# STM32Fx.net
KiCad netlist of a schematic drawn in Altium Designer
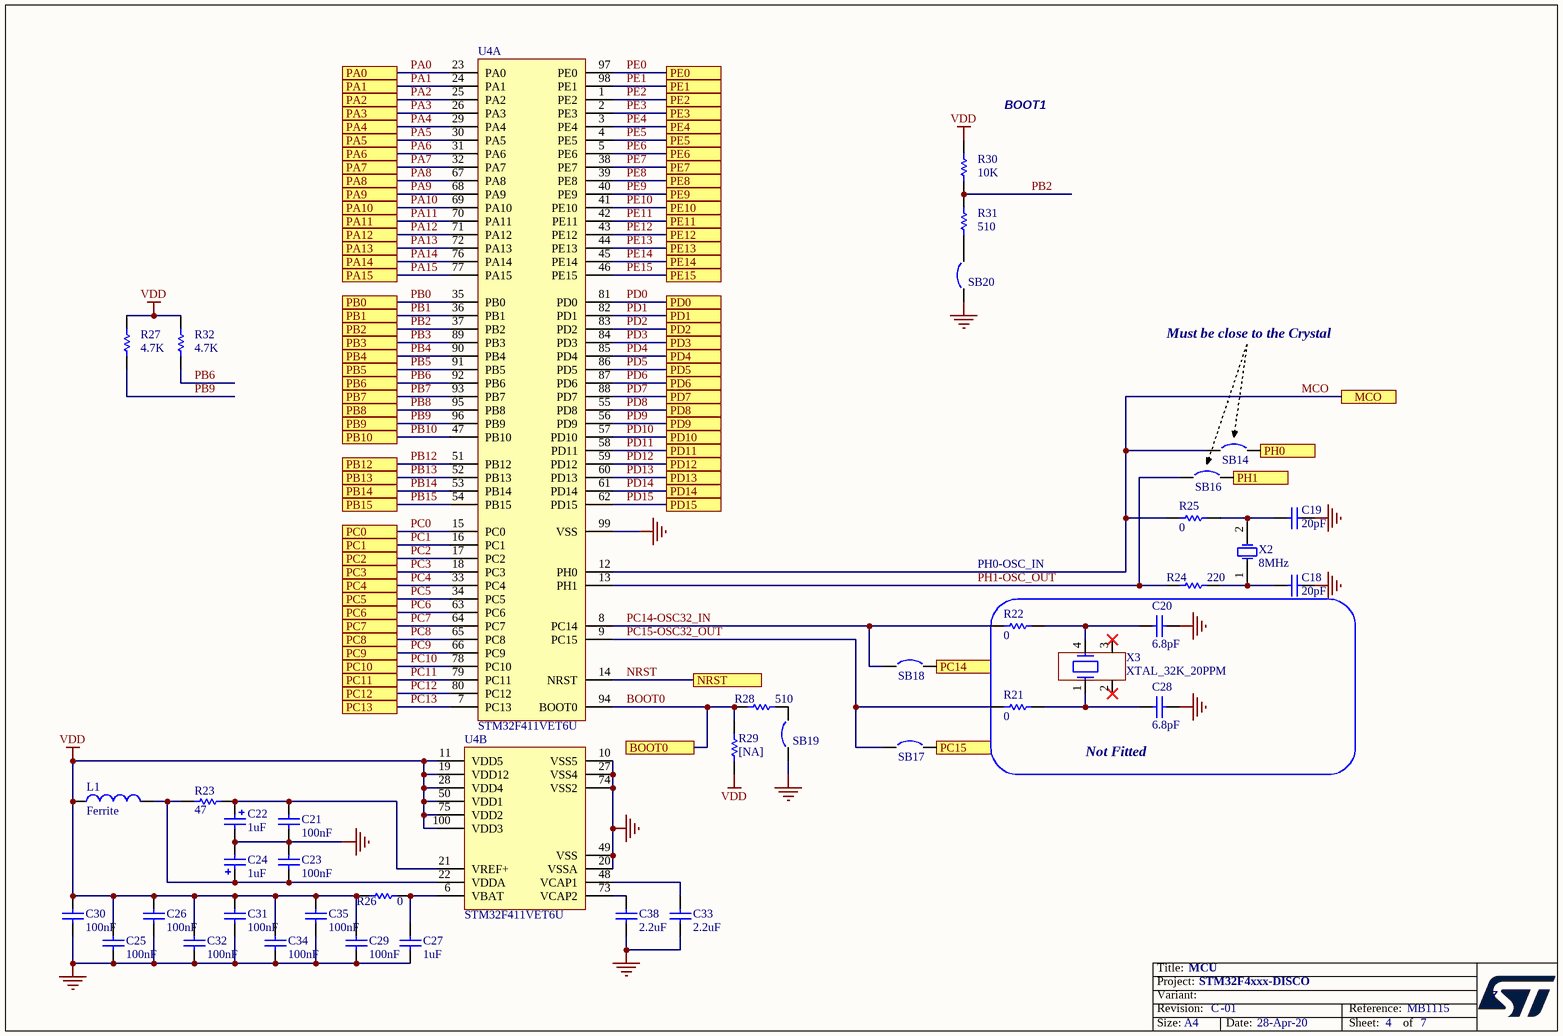
[diagram p0: STM32Fx.SchDoc]

(export (version "E")
  (design (tool "Eeschema 10.0.6"))
  (components
    (comp (ref "C18")
      (value "20pF")
      (footprint "0402C (Primary)")
      (description "Capacitor,20pF,50V,NPO,5%,0402,YAGEO")
      (libsource (lib "MCD_TOOLS") (part "Cap_20pF_NPO_5%_0402"))
    )
    (comp (ref "C19")
      (value "20pF")
      (footprint "0402C (Primary)")
      (description "Capacitor,20pF,50V,NPO,5%,0402,YAGEO")
      (libsource (lib "MCD_TOOLS") (part "Cap_20pF_NPO_5%_0402"))
    )
    (comp (ref "C20")
      (value "6.8pF")
      (footprint "0402C (Primary)")
      (description "Capacitor,6.8pF,50V,NPO,4%,0402,AVX")
      (libsource (lib "MCD_TOOLS") (part "Cap_6.8pF_NPO_4%_0402"))
    )
    (comp (ref "C21")
      (value "100nF")
      (footprint "0402C (Primary)")
      (description "Capacitor,100nF,16V,X7R,10%,0402,YAGEO")
      (libsource (lib "MCD_TOOLS") (part "Cap_100nF_X7R_10%_0402"))
    )
    (comp (ref "C22")
      (value "1uF")
      (footprint "TAN-A (Primary)")
      (description "Polarized Capacitor,1uF,16V,10%,typeA,AVX")
      (libsource (lib "MCD_TOOLS") (part "Cap_1uF_POL_10%_TANA"))
    )
    (comp (ref "C23")
      (value "100nF")
      (footprint "0402C (Primary)")
      (description "Capacitor,100nF,16V,X7R,10%,0402,YAGEO")
      (libsource (lib "MCD_TOOLS") (part "Cap_100nF_X7R_10%_0402"))
    )
    (comp (ref "C24")
      (value "1uF")
      (footprint "TAN-A (Primary)")
      (description "Polarized Capacitor,1uF,16V,10%,typeA,AVX")
      (libsource (lib "MCD_TOOLS") (part "Cap_1uF_POL_10%_TANA"))
    )
    (comp (ref "C25")
      (value "100nF")
      (footprint "0402C (Primary)")
      (description "Capacitor,100nF,16V,X7R,10%,0402,YAGEO")
      (libsource (lib "MCD_TOOLS") (part "Cap_100nF_X7R_10%_0402"))
    )
    (comp (ref "C26")
      (value "100nF")
      (footprint "0402C (Primary)")
      (description "Capacitor,100nF,16V,X7R,10%,0402,YAGEO")
      (libsource (lib "MCD_TOOLS") (part "Cap_100nF_X7R_10%_0402"))
    )
    (comp (ref "C27")
      (value "1uF")
      (footprint "0603C (Primary)")
      (description "Capacitor,1uF,16V,X5R,10%,0603,YAGEO")
      (libsource (lib "MCD_TOOLS") (part "Cap_1uF_X5R_10%_0603"))
    )
    (comp (ref "C28")
      (value "6.8pF")
      (footprint "0402C (Primary)")
      (description "Capacitor,6.8pF,50V,NPO,4%,0402,AVX")
      (libsource (lib "MCD_TOOLS") (part "Cap_6.8pF_NPO_4%_0402"))
    )
    (comp (ref "C29")
      (value "100nF")
      (footprint "0402C (Primary)")
      (description "Capacitor,100nF,16V,X7R,10%,0402,YAGEO")
      (libsource (lib "MCD_TOOLS") (part "Cap_100nF_X7R_10%_0402"))
    )
    (comp (ref "C30")
      (value "100nF")
      (footprint "0402C (Primary)")
      (description "Capacitor,100nF,16V,X7R,10%,0402,YAGEO")
      (libsource (lib "MCD_TOOLS") (part "Cap_100nF_X7R_10%_0402"))
    )
    (comp (ref "C31")
      (value "100nF")
      (footprint "0402C (Primary)")
      (description "Capacitor,100nF,16V,X7R,10%,0402,YAGEO")
      (libsource (lib "MCD_TOOLS") (part "Cap_100nF_X7R_10%_0402"))
    )
    (comp (ref "C32")
      (value "100nF")
      (footprint "0402C (Primary)")
      (description "Capacitor,100nF,16V,X7R,10%,0402,YAGEO")
      (libsource (lib "MCD_TOOLS") (part "Cap_100nF_X7R_10%_0402"))
    )
    (comp (ref "C33")
      (value "2.2uF")
      (footprint "TAN-A (Primary)")
      (description "Capacitor,2.2uF,16V, X7R,10%,0805,YAGEO")
      (libsource (lib "MCD_TOOLS") (part "Cap_2.2uF_X7R_10%_0805"))
    )
    (comp (ref "C34")
      (value "100nF")
      (footprint "0402C (Primary)")
      (description "Capacitor,100nF,16V,X7R,10%,0402,YAGEO")
      (libsource (lib "MCD_TOOLS") (part "Cap_100nF_X7R_10%_0402"))
    )
    (comp (ref "C35")
      (value "100nF")
      (footprint "0402C (Primary)")
      (description "Capacitor,100nF,16V,X7R,10%,0402,YAGEO")
      (libsource (lib "MCD_TOOLS") (part "Cap_100nF_X7R_10%_0402"))
    )
    (comp (ref "C38")
      (value "2.2uF")
      (footprint "TAN-A (Primary)")
      (description "Capacitor,2.2uF,16V, X7R,10%,0805,YAGEO")
      (libsource (lib "MCD_TOOLS") (part "Cap_2.2uF_X7R_10%_0805"))
    )
    (comp (ref "L1")
      (value "Ferrite")
      (footprint "0603L (Primary)")
      (description "Bead,600R,350mA,0603,FCM1608KF-601T03,Tai-tech")
      (libsource (lib "MCD_TOOLS") (part "BEAD_600R_350MA_0603"))
    )
    (comp (ref "R21")
      (value "0")
      (footprint "0402R (Primary)")
      (description "Resistor,0,0402")
      (libsource (lib "MCD_TOOLS") (part "Res_0_0402"))
    )
    (comp (ref "R22")
      (value "0")
      (footprint "0402R (Primary)")
      (description "Resistor,0,0402")
      (libsource (lib "MCD_TOOLS") (part "Res_0_0402"))
    )
    (comp (ref "R23")
      (value "47")
      (footprint "0402R (Primary)")
      (description "Resistor")
      (fields (field (name "PUBLISHER") "Altium Limited"))
      (libsource (lib "Miscellaneous Devices") (part "Res1"))
    )
    (comp (ref "R24")
      (value "220")
      (footprint "0402R (Primary)")
      (description "Resistor")
      (fields (field (name "PUBLISHER") "Altium Limited"))
      (libsource (lib "Miscellaneous Devices") (part "Res1"))
    )
    (comp (ref "R25")
      (value "0")
      (footprint "0402R (Primary)")
      (description "Resistor,0,0402")
      (libsource (lib "MCD_TOOLS") (part "Res_0_0402"))
    )
    (comp (ref "R26")
      (value "0")
      (footprint "0402R (Primary)")
      (description "Resistor,0,0402")
      (libsource (lib "MCD_TOOLS") (part "Res_0_0402"))
    )
    (comp (ref "R27")
      (value "4.7K")
      (footprint "0402R (Primary)")
      (description "Resistor")
      (fields (field (name "PUBLISHER") "Altium Limited"))
      (libsource (lib "Miscellaneous Devices") (part "res1"))
    )
    (comp (ref "R28")
      (value "510")
      (footprint "0402R (Primary)")
      (description "Resistor")
      (fields (field (name "PUBLISHER") "Altium Limited"))
      (libsource (lib "Miscellaneous Devices") (part "Res1"))
    )
    (comp (ref "R29")
      (value "[NA]")
      (footprint "0402R (Primary)")
      (description "Resistor,[NA],0402")
      (libsource (lib "MCD_TOOLS") (part "Res_NA_0402"))
    )
    (comp (ref "R30")
      (value "10K")
      (footprint "0402R (Primary)")
      (description "Resistor")
      (fields (field (name "PUBLISHER") "Altium Limited"))
      (libsource (lib "Miscellaneous Devices") (part "res1"))
    )
    (comp (ref "R31")
      (value "510")
      (footprint "0402R (Primary)")
      (description "Resistor")
      (fields (field (name "PUBLISHER") "Altium Limited"))
      (libsource (lib "Miscellaneous Devices") (part "res1"))
    )
    (comp (ref "R32")
      (value "4.7K")
      (footprint "0402R (Primary)")
      (description "Resistor")
      (fields (field (name "PUBLISHER") "Altium Limited"))
      (libsource (lib "Miscellaneous Devices") (part "res1"))
    )
    (comp (ref "SB14")
      (value "Circuit Breaker")
      (footprint "JP2_SMD (Primary)")
      (libsource (lib "MCD_TOOLS") (part "Circuit Breaker"))
    )
    (comp (ref "SB16")
      (value "Circuit Breaker")
      (footprint "JP2_SMD (Primary)")
      (libsource (lib "MCD_TOOLS") (part "Circuit Breaker"))
    )
    (comp (ref "SB17")
      (value "Circuit Breaker")
      (footprint "JP2_SMD (Primary)")
      (libsource (lib "MCD_TOOLS") (part "Circuit Breaker"))
    )
    (comp (ref "SB18")
      (value "Circuit Breaker")
      (footprint "JP2_SMD (Primary)")
      (libsource (lib "MCD_TOOLS") (part "Circuit Breaker"))
    )
    (comp (ref "SB19")
      (value "Circuit Breaker")
      (footprint "JP2_SMD (Primary)")
      (libsource (lib "MCD_TOOLS") (part "Circuit Breaker"))
    )
    (comp (ref "SB20")
      (value "Circuit Breaker")
      (footprint "JP2_SMD (Primary)")
      (libsource (lib "MCD_TOOLS") (part "Circuit Breaker"))
    )
    (comp (ref "U4")
      (value "STM32F411VET6U")
      (footprint "TQFP100_14X14 (Primary)")
      (description "STM32 Tiny Manta (STM32F401VCT6U)")
      (libsource (lib "MCD_TOOLS") (part "STM32F401VCT6U"))
    )
    (comp (ref "X2")
      (value "8MHz")
      (footprint "XTAL1 (Primary)")
      (description "Crystal Oscillator,8Mhz,20PF,20PPM,-10-70 degree,DIP,HC-49S")
      (libsource (lib "MCD_TOOLS") (part "XTAL_8MHZ_20PPM"))
    )
    (comp (ref "X3")
      (value "XTAL_32K_20PPM")
      (footprint "MC306-CRYSTAL (Primary)")
      (description "Crystal oscillator for clock,32.768K,6PF,20PPM,-40~85 degree,SMT")
      (libsource (lib "MCD_TOOLS") (part "XTAL_32K"))
    )
  )
  (nets
    (net (code "1") (name "/BOOT0") (class "Default")
      (node (ref "R28") (pin "2") (pinfunction "2_2") (pintype "passive"))
      (node (ref "R29") (pin "2") (pinfunction "2_2") (pintype "passive"))
      (node (ref "U4") (pin "94") (pinfunction "BOOT0_94") (pintype "passive"))
    )
    (net (code "2") (name "/MCO") (class "Default")
      (node (ref "R25") (pin "1") (pinfunction "1_1") (pintype "passive"))
      (node (ref "SB14") (pin "1") (pinfunction "1_1") (pintype "passive"))
      (node (ref "U4") (pin "12") (pinfunction "PH0_12") (pintype "passive"))
    )
    (net (code "3") (name "/NRST") (class "Default")
      (node (ref "U4") (pin "14") (pinfunction "NRST_14") (pintype "passive"))
    )
    (net (code "4") (name "/PA0") (class "Default")
      (node (ref "U4") (pin "23") (pinfunction "PA0_23") (pintype "passive"))
    )
    (net (code "5") (name "/PA1") (class "Default")
      (node (ref "U4") (pin "24") (pinfunction "PA1_24") (pintype "passive"))
    )
    (net (code "6") (name "/PA2") (class "Default")
      (node (ref "U4") (pin "25") (pinfunction "PA2_25") (pintype "passive"))
    )
    (net (code "7") (name "/PA3") (class "Default")
      (node (ref "U4") (pin "26") (pinfunction "PA3_26") (pintype "passive"))
    )
    (net (code "8") (name "/PA4") (class "Default")
      (node (ref "U4") (pin "29") (pinfunction "PA4_29") (pintype "passive"))
    )
    (net (code "9") (name "/PA5") (class "Default")
      (node (ref "U4") (pin "30") (pinfunction "PA5_30") (pintype "passive"))
    )
    (net (code "10") (name "/PA6") (class "Default")
      (node (ref "U4") (pin "31") (pinfunction "PA6_31") (pintype "passive"))
    )
    (net (code "11") (name "/PA7") (class "Default")
      (node (ref "U4") (pin "32") (pinfunction "PA7_32") (pintype "passive"))
    )
    (net (code "12") (name "/PA8") (class "Default")
      (node (ref "U4") (pin "67") (pinfunction "PA8_67") (pintype "passive"))
    )
    (net (code "13") (name "/PA9") (class "Default")
      (node (ref "U4") (pin "68") (pinfunction "PA9_68") (pintype "passive"))
    )
    (net (code "14") (name "/PA10") (class "Default")
      (node (ref "U4") (pin "69") (pinfunction "PA10_69") (pintype "passive"))
    )
    (net (code "15") (name "/PA11") (class "Default")
      (node (ref "U4") (pin "70") (pinfunction "PA11_70") (pintype "passive"))
    )
    (net (code "16") (name "/PA12") (class "Default")
      (node (ref "U4") (pin "71") (pinfunction "PA12_71") (pintype "passive"))
    )
    (net (code "17") (name "/PA13") (class "Default")
      (node (ref "U4") (pin "72") (pinfunction "PA13_72") (pintype "passive"))
    )
    (net (code "18") (name "/PA14") (class "Default")
      (node (ref "U4") (pin "76") (pinfunction "PA14_76") (pintype "passive"))
    )
    (net (code "19") (name "/PA15") (class "Default")
      (node (ref "U4") (pin "77") (pinfunction "PA15_77") (pintype "passive"))
    )
    (net (code "20") (name "/PB0") (class "Default")
      (node (ref "U4") (pin "35") (pinfunction "PB0_35") (pintype "passive"))
    )
    (net (code "21") (name "/PB1") (class "Default")
      (node (ref "U4") (pin "36") (pinfunction "PB1_36") (pintype "passive"))
    )
    (net (code "22") (name "/PB2") (class "Default")
      (node (ref "R30") (pin "2") (pinfunction "2_2") (pintype "passive"))
      (node (ref "R31") (pin "1") (pinfunction "1_1") (pintype "passive"))
      (node (ref "U4") (pin "37") (pinfunction "PB2_37") (pintype "passive"))
    )
    (net (code "23") (name "/PB3") (class "Default")
      (node (ref "U4") (pin "89") (pinfunction "PB3_89") (pintype "passive"))
    )
    (net (code "24") (name "/PB4") (class "Default")
      (node (ref "U4") (pin "90") (pinfunction "PB4_90") (pintype "passive"))
    )
    (net (code "25") (name "/PB5") (class "Default")
      (node (ref "U4") (pin "91") (pinfunction "PB5_91") (pintype "passive"))
    )
    (net (code "26") (name "/PB6") (class "Default")
      (node (ref "R32") (pin "2") (pinfunction "2_2") (pintype "passive"))
      (node (ref "U4") (pin "92") (pinfunction "PB6_92") (pintype "passive"))
    )
    (net (code "27") (name "/PB7") (class "Default")
      (node (ref "U4") (pin "93") (pinfunction "PB7_93") (pintype "passive"))
    )
    (net (code "28") (name "/PB8") (class "Default")
      (node (ref "U4") (pin "95") (pinfunction "PB8_95") (pintype "passive"))
    )
    (net (code "29") (name "/PB9") (class "Default")
      (node (ref "R27") (pin "2") (pinfunction "2_2") (pintype "passive"))
      (node (ref "U4") (pin "96") (pinfunction "PB9_96") (pintype "passive"))
    )
    (net (code "30") (name "/PB10") (class "Default")
      (node (ref "U4") (pin "47") (pinfunction "PB10_47") (pintype "passive"))
    )
    (net (code "31") (name "/PB12") (class "Default")
      (node (ref "U4") (pin "51") (pinfunction "PB12_51") (pintype "passive"))
    )
    (net (code "32") (name "/PB13") (class "Default")
      (node (ref "U4") (pin "52") (pinfunction "PB13_52") (pintype "passive"))
    )
    (net (code "33") (name "/PB14") (class "Default")
      (node (ref "U4") (pin "53") (pinfunction "PB14_53") (pintype "passive"))
    )
    (net (code "34") (name "/PB15") (class "Default")
      (node (ref "U4") (pin "54") (pinfunction "PB15_54") (pintype "passive"))
    )
    (net (code "35") (name "/PC0") (class "Default")
      (node (ref "U4") (pin "15") (pinfunction "PC0_15") (pintype "passive"))
    )
    (net (code "36") (name "/PC1") (class "Default")
      (node (ref "U4") (pin "16") (pinfunction "PC1_16") (pintype "passive"))
    )
    (net (code "37") (name "/PC2") (class "Default")
      (node (ref "U4") (pin "17") (pinfunction "PC2_17") (pintype "passive"))
    )
    (net (code "38") (name "/PC3") (class "Default")
      (node (ref "U4") (pin "18") (pinfunction "PC3_18") (pintype "passive"))
    )
    (net (code "39") (name "/PC4") (class "Default")
      (node (ref "U4") (pin "33") (pinfunction "PC4_33") (pintype "passive"))
    )
    (net (code "40") (name "/PC5") (class "Default")
      (node (ref "U4") (pin "34") (pinfunction "PC5_34") (pintype "passive"))
    )
    (net (code "41") (name "/PC6") (class "Default")
      (node (ref "U4") (pin "63") (pinfunction "PC6_63") (pintype "passive"))
    )
    (net (code "42") (name "/PC7") (class "Default")
      (node (ref "U4") (pin "64") (pinfunction "PC7_64") (pintype "passive"))
    )
    (net (code "43") (name "/PC8") (class "Default")
      (node (ref "U4") (pin "65") (pinfunction "PC8_65") (pintype "passive"))
    )
    (net (code "44") (name "/PC9") (class "Default")
      (node (ref "U4") (pin "66") (pinfunction "PC9_66") (pintype "passive"))
    )
    (net (code "45") (name "/PC10") (class "Default")
      (node (ref "U4") (pin "78") (pinfunction "PC10_78") (pintype "passive"))
    )
    (net (code "46") (name "/PC11") (class "Default")
      (node (ref "U4") (pin "79") (pinfunction "PC11_79") (pintype "passive"))
    )
    (net (code "47") (name "/PC12") (class "Default")
      (node (ref "U4") (pin "80") (pinfunction "PC12_80") (pintype "passive"))
    )
    (net (code "48") (name "/PC13") (class "Default")
      (node (ref "U4") (pin "7") (pinfunction "PC13_7") (pintype "passive"))
    )
    (net (code "49") (name "/PC14") (class "Default")
      (node (ref "SB18") (pin "2") (pinfunction "2_2") (pintype "passive"))
    )
    (net (code "50") (name "/PC14-OSC32_IN") (class "Default")
      (node (ref "R22") (pin "1") (pinfunction "1_1") (pintype "passive"))
      (node (ref "SB18") (pin "1") (pinfunction "1_1") (pintype "passive"))
      (node (ref "U4") (pin "8") (pinfunction "PC14_8") (pintype "passive"))
    )
    (net (code "51") (name "/PC15") (class "Default")
      (node (ref "SB17") (pin "2") (pinfunction "2_2") (pintype "passive"))
    )
    (net (code "52") (name "/PC15-OSC32_OUT") (class "Default")
      (node (ref "R21") (pin "1") (pinfunction "1_1") (pintype "passive"))
      (node (ref "SB17") (pin "1") (pinfunction "1_1") (pintype "passive"))
      (node (ref "U4") (pin "9") (pinfunction "PC15_9") (pintype "passive"))
    )
    (net (code "53") (name "/PD0") (class "Default")
      (node (ref "U4") (pin "81") (pinfunction "PD0_81") (pintype "passive"))
    )
    (net (code "54") (name "/PD1") (class "Default")
      (node (ref "U4") (pin "82") (pinfunction "PD1_82") (pintype "passive"))
    )
    (net (code "55") (name "/PD2") (class "Default")
      (node (ref "U4") (pin "83") (pinfunction "PD2_83") (pintype "passive"))
    )
    (net (code "56") (name "/PD3") (class "Default")
      (node (ref "U4") (pin "84") (pinfunction "PD3_84") (pintype "passive"))
    )
    (net (code "57") (name "/PD4") (class "Default")
      (node (ref "U4") (pin "85") (pinfunction "PD4_85") (pintype "passive"))
    )
    (net (code "58") (name "/PD5") (class "Default")
      (node (ref "U4") (pin "86") (pinfunction "PD5_86") (pintype "passive"))
    )
    (net (code "59") (name "/PD6") (class "Default")
      (node (ref "U4") (pin "87") (pinfunction "PD6_87") (pintype "passive"))
    )
    (net (code "60") (name "/PD7") (class "Default")
      (node (ref "U4") (pin "88") (pinfunction "PD7_88") (pintype "passive"))
    )
    (net (code "61") (name "/PD8") (class "Default")
      (node (ref "U4") (pin "55") (pinfunction "PD8_55") (pintype "passive"))
    )
    (net (code "62") (name "/PD9") (class "Default")
      (node (ref "U4") (pin "56") (pinfunction "PD9_56") (pintype "passive"))
    )
    (net (code "63") (name "/PD10") (class "Default")
      (node (ref "U4") (pin "57") (pinfunction "PD10_57") (pintype "passive"))
    )
    (net (code "64") (name "/PD11") (class "Default")
      (node (ref "U4") (pin "58") (pinfunction "PD11_58") (pintype "passive"))
    )
    (net (code "65") (name "/PD12") (class "Default")
      (node (ref "U4") (pin "59") (pinfunction "PD12_59") (pintype "passive"))
    )
    (net (code "66") (name "/PD13") (class "Default")
      (node (ref "U4") (pin "60") (pinfunction "PD13_60") (pintype "passive"))
    )
    (net (code "67") (name "/PD14") (class "Default")
      (node (ref "U4") (pin "61") (pinfunction "PD14_61") (pintype "passive"))
    )
    (net (code "68") (name "/PD15") (class "Default")
      (node (ref "U4") (pin "62") (pinfunction "PD15_62") (pintype "passive"))
    )
    (net (code "69") (name "/PE0") (class "Default")
      (node (ref "U4") (pin "97") (pinfunction "PE0_97") (pintype "passive"))
    )
    (net (code "70") (name "/PE1") (class "Default")
      (node (ref "U4") (pin "98") (pinfunction "PE1_98") (pintype "passive"))
    )
    (net (code "71") (name "/PE2") (class "Default")
      (node (ref "U4") (pin "1") (pinfunction "PE2_1") (pintype "passive"))
    )
    (net (code "72") (name "/PE3") (class "Default")
      (node (ref "U4") (pin "2") (pinfunction "PE3_2") (pintype "passive"))
    )
    (net (code "73") (name "/PE4") (class "Default")
      (node (ref "U4") (pin "3") (pinfunction "PE4_3") (pintype "passive"))
    )
    (net (code "74") (name "/PE5") (class "Default")
      (node (ref "U4") (pin "4") (pinfunction "PE5_4") (pintype "passive"))
    )
    (net (code "75") (name "/PE6") (class "Default")
      (node (ref "U4") (pin "5") (pinfunction "PE6_5") (pintype "passive"))
    )
    (net (code "76") (name "/PE7") (class "Default")
      (node (ref "U4") (pin "38") (pinfunction "PE7_38") (pintype "passive"))
    )
    (net (code "77") (name "/PE8") (class "Default")
      (node (ref "U4") (pin "39") (pinfunction "PE8_39") (pintype "passive"))
    )
    (net (code "78") (name "/PE9") (class "Default")
      (node (ref "U4") (pin "40") (pinfunction "PE9_40") (pintype "passive"))
    )
    (net (code "79") (name "/PE10") (class "Default")
      (node (ref "U4") (pin "41") (pinfunction "PE10_41") (pintype "passive"))
    )
    (net (code "80") (name "/PE11") (class "Default")
      (node (ref "U4") (pin "42") (pinfunction "PE11_42") (pintype "passive"))
    )
    (net (code "81") (name "/PE12") (class "Default")
      (node (ref "U4") (pin "43") (pinfunction "PE12_43") (pintype "passive"))
    )
    (net (code "82") (name "/PE13") (class "Default")
      (node (ref "U4") (pin "44") (pinfunction "PE13_44") (pintype "passive"))
    )
    (net (code "83") (name "/PE14") (class "Default")
      (node (ref "U4") (pin "45") (pinfunction "PE14_45") (pintype "passive"))
    )
    (net (code "84") (name "/PE15") (class "Default")
      (node (ref "U4") (pin "46") (pinfunction "PE15_46") (pintype "passive"))
    )
    (net (code "85") (name "/PH0") (class "Default")
      (node (ref "SB14") (pin "2") (pinfunction "2_2") (pintype "passive"))
    )
    (net (code "86") (name "/PH1") (class "Default")
      (node (ref "SB16") (pin "2") (pinfunction "2_2") (pintype "passive"))
    )
    (net (code "87") (name "/PH1-OSC_OUT") (class "Default")
      (node (ref "R24") (pin "2") (pinfunction "2_2") (pintype "passive"))
      (node (ref "SB16") (pin "1") (pinfunction "1_1") (pintype "passive"))
      (node (ref "U4") (pin "13") (pinfunction "PH1_13") (pintype "passive"))
    )
    (net (code "88") (name "GND") (class "Default")
      (node (ref "C18") (pin "1") (pinfunction "1_1") (pintype "passive"))
      (node (ref "C19") (pin "1") (pinfunction "1_1") (pintype "passive"))
      (node (ref "C20") (pin "2") (pinfunction "2_2") (pintype "passive"))
      (node (ref "C21") (pin "1") (pinfunction "1_1") (pintype "passive"))
      (node (ref "C22") (pin "2") (pinfunction "2_2") (pintype "passive"))
      (node (ref "C23") (pin "1") (pinfunction "1_1") (pintype "passive"))
      (node (ref "C24") (pin "2") (pinfunction "2_2") (pintype "passive"))
      (node (ref "C25") (pin "1") (pinfunction "1_1") (pintype "passive"))
      (node (ref "C26") (pin "2") (pinfunction "2_2") (pintype "passive"))
      (node (ref "C27") (pin "2") (pinfunction "2_2") (pintype "passive"))
      (node (ref "C28") (pin "2") (pinfunction "2_2") (pintype "passive"))
      (node (ref "C29") (pin "1") (pinfunction "1_1") (pintype "passive"))
      (node (ref "C30") (pin "1") (pinfunction "1_1") (pintype "passive"))
      (node (ref "C31") (pin "1") (pinfunction "1_1") (pintype "passive"))
      (node (ref "C32") (pin "1") (pinfunction "1_1") (pintype "passive"))
      (node (ref "C33") (pin "2") (pinfunction "2_2") (pintype "passive"))
      (node (ref "C34") (pin "1") (pinfunction "1_1") (pintype "passive"))
      (node (ref "C35") (pin "2") (pinfunction "2_2") (pintype "passive"))
      (node (ref "C38") (pin "2") (pinfunction "2_2") (pintype "passive"))
      (node (ref "SB19") (pin "1") (pinfunction "1_1") (pintype "passive"))
      (node (ref "SB20") (pin "1") (pinfunction "1_1") (pintype "passive"))
      (node (ref "U4") (pin "10") (pinfunction "VSS5_10") (pintype "passive"))
      (node (ref "U4") (pin "20") (pinfunction "VSSA_20") (pintype "passive"))
      (node (ref "U4") (pin "27") (pinfunction "VSS4_27") (pintype "passive"))
      (node (ref "U4") (pin "49") (pinfunction "VSS_49") (pintype "passive"))
      (node (ref "U4") (pin "74") (pinfunction "VSS2_74") (pintype "passive"))
      (node (ref "U4") (pin "99") (pinfunction "VSS_99") (pintype "passive"))
    )
    (net (code "89") (name "Net-(C20-Pad1)") (class "Default")
      (node (ref "C20") (pin "1") (pinfunction "1_1") (pintype "passive"))
      (node (ref "R22") (pin "2") (pinfunction "2_2") (pintype "passive"))
      (node (ref "X3") (pin "4") (pinfunction "4_4") (pintype "passive"))
    )
    (net (code "90") (name "Net-(C28-Pad1)") (class "Default")
      (node (ref "C28") (pin "1") (pinfunction "1_1") (pintype "passive"))
      (node (ref "R21") (pin "2") (pinfunction "2_2") (pintype "passive"))
      (node (ref "X3") (pin "1") (pinfunction "1_1") (pintype "passive"))
    )
    (net (code "91") (name "Net-(R28-Pad1)") (class "Default")
      (node (ref "R28") (pin "1") (pinfunction "1_1") (pintype "passive"))
      (node (ref "SB19") (pin "2") (pinfunction "2_2") (pintype "passive"))
    )
    (net (code "92") (name "Net-(R31-Pad2)") (class "Default")
      (node (ref "R31") (pin "2") (pinfunction "2_2") (pintype "passive"))
      (node (ref "SB20") (pin "2") (pinfunction "2_2") (pintype "passive"))
    )
    (net (code "93") (name "Net-(U4B-VBAT)") (class "Default")
      (node (ref "C27") (pin "1") (pinfunction "1_1") (pintype "passive"))
      (node (ref "R26") (pin "2") (pinfunction "2_2") (pintype "passive"))
      (node (ref "U4") (pin "6") (pinfunction "VBAT_6") (pintype "passive"))
    )
    (net (code "94") (name "Net-(U4B-VCAP1)") (class "Default")
      (node (ref "C33") (pin "1") (pinfunction "1_1") (pintype "passive"))
      (node (ref "U4") (pin "48") (pinfunction "VCAP1_48") (pintype "passive"))
    )
    (net (code "95") (name "Net-(U4B-VCAP2)") (class "Default")
      (node (ref "C38") (pin "1") (pinfunction "1_1") (pintype "passive"))
      (node (ref "U4") (pin "73") (pinfunction "VCAP2_73") (pintype "passive"))
    )
    (net (code "96") (name "Net-(U4B-VDDA)") (class "Default")
      (node (ref "C23") (pin "2") (pinfunction "2_2") (pintype "passive"))
      (node (ref "C24") (pin "1") (pinfunction "1_1") (pintype "passive"))
      (node (ref "L1") (pin "2") (pinfunction "2_2") (pintype "passive"))
      (node (ref "R23") (pin "2") (pinfunction "2_2") (pintype "passive"))
      (node (ref "U4") (pin "22") (pinfunction "VDDA_22") (pintype "passive"))
    )
    (net (code "97") (name "Net-(U4B-VREF+)") (class "Default")
      (node (ref "C21") (pin "2") (pinfunction "2_2") (pintype "passive"))
      (node (ref "C22") (pin "1") (pinfunction "1_1") (pintype "passive"))
      (node (ref "R23") (pin "1") (pinfunction "1_1") (pintype "passive"))
      (node (ref "U4") (pin "21") (pinfunction "VREF+_21") (pintype "passive"))
    )
    (net (code "98") (name "Net-(X2-OSC1)") (class "Default")
      (node (ref "C18") (pin "2") (pinfunction "2_2") (pintype "passive"))
      (node (ref "R24") (pin "1") (pinfunction "1_1") (pintype "passive"))
      (node (ref "X2") (pin "1") (pinfunction "OSC1_1") (pintype "passive"))
    )
    (net (code "99") (name "Net-(X2-OSC2)") (class "Default")
      (node (ref "C19") (pin "2") (pinfunction "2_2") (pintype "passive"))
      (node (ref "R25") (pin "2") (pinfunction "2_2") (pintype "passive"))
      (node (ref "X2") (pin "2") (pinfunction "OSC2_2") (pintype "passive"))
    )
    (net (code "100") (name "VDD") (class "Default")
      (node (ref "C25") (pin "2") (pinfunction "2_2") (pintype "passive"))
      (node (ref "C26") (pin "1") (pinfunction "1_1") (pintype "passive"))
      (node (ref "C29") (pin "2") (pinfunction "2_2") (pintype "passive"))
      (node (ref "C30") (pin "2") (pinfunction "2_2") (pintype "passive"))
      (node (ref "C31") (pin "2") (pinfunction "2_2") (pintype "passive"))
      (node (ref "C32") (pin "2") (pinfunction "2_2") (pintype "passive"))
      (node (ref "C34") (pin "2") (pinfunction "2_2") (pintype "passive"))
      (node (ref "C35") (pin "1") (pinfunction "1_1") (pintype "passive"))
      (node (ref "L1") (pin "1") (pinfunction "1_1") (pintype "passive"))
      (node (ref "R26") (pin "1") (pinfunction "1_1") (pintype "passive"))
      (node (ref "R27") (pin "1") (pinfunction "1_1") (pintype "passive"))
      (node (ref "R29") (pin "1") (pinfunction "1_1") (pintype "passive"))
      (node (ref "R30") (pin "1") (pinfunction "1_1") (pintype "passive"))
      (node (ref "R32") (pin "1") (pinfunction "1_1") (pintype "passive"))
      (node (ref "U4") (pin "100") (pinfunction "VDD3_100") (pintype "passive"))
      (node (ref "U4") (pin "11") (pinfunction "VDD5_11") (pintype "passive"))
      (node (ref "U4") (pin "19") (pinfunction "VDD12_19") (pintype "passive"))
      (node (ref "U4") (pin "28") (pinfunction "VDD4_28") (pintype "passive"))
      (node (ref "U4") (pin "50") (pinfunction "VDD1_50") (pintype "passive"))
      (node (ref "U4") (pin "75") (pinfunction "VDD2_75") (pintype "passive"))
    )
    (net (code "101") (name "unconnected-(X3-Pad2)") (class "Default")
      (node (ref "X3") (pin "2") (pinfunction "2_2") (pintype "passive+no_connect"))
    )
    (net (code "102") (name "unconnected-(X3-Pad3)") (class "Default")
      (node (ref "X3") (pin "3") (pinfunction "3_3") (pintype "passive+no_connect"))
    )
  )
)
